# switch_vn9e30f.net
KiCad netlist of a schematic drawn in Altium Designer
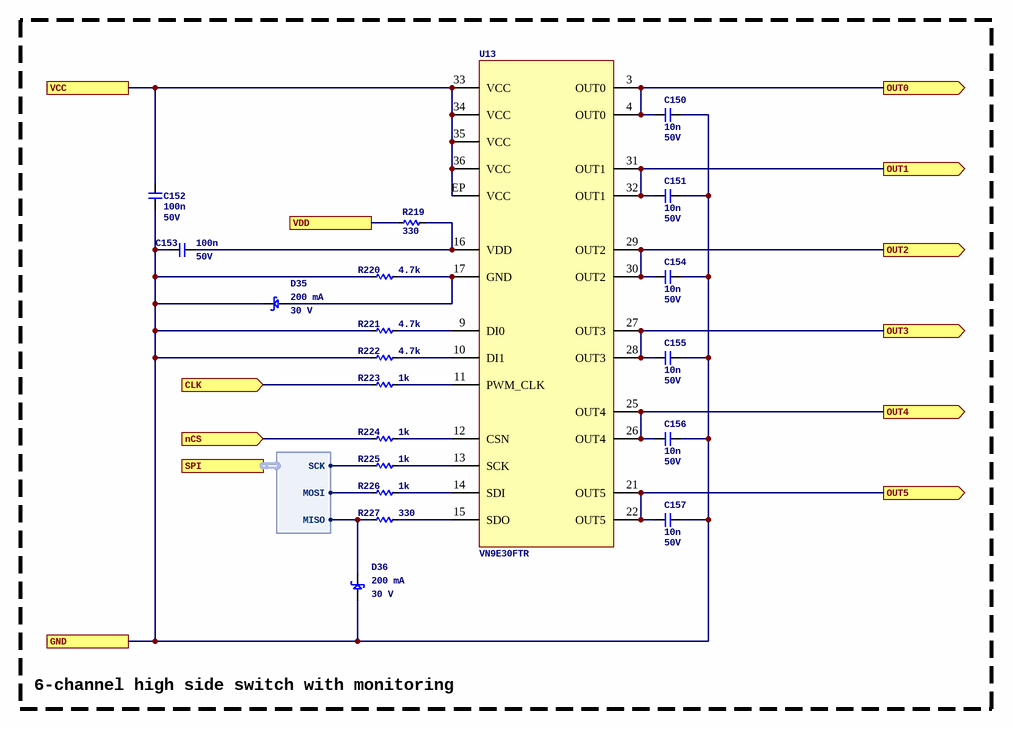
[diagram p0: switch_vn9e30f.SchDoc]

(export (version "E")
  (design (tool "Eeschema 10.0.6"))
  (components
    (comp (ref "C150")
      (value "CL05B103KB5NNNC")
      (footprint "C0402")
      (fields
        (field (name "CAPACITANCE") "10n")
        (field (name "MANUFACTURER") "Samsung Electro-Mechanics")
        (field (name "VOLTAGE RATING") "50V")
      )
      (libsource (lib "database") (part "__template_cap"))
    )
    (comp (ref "C151")
      (value "CL05B103KB5NNNC")
      (footprint "C0402")
      (fields
        (field (name "CAPACITANCE") "10n")
        (field (name "MANUFACTURER") "Samsung Electro-Mechanics")
        (field (name "VOLTAGE RATING") "50V")
      )
      (libsource (lib "database") (part "__template_cap"))
    )
    (comp (ref "C152")
      (value "CL05B104KB54PNC")
      (footprint "C0402")
      (fields
        (field (name "CAPACITANCE") "100n")
        (field (name "MANUFACTURER") "Samsung Electro-Mechanics")
        (field (name "VOLTAGE RATING") "50V")
      )
      (libsource (lib "database") (part "__template_cap"))
    )
    (comp (ref "C153")
      (value "CL05B104KB54PNC")
      (footprint "C0402")
      (fields
        (field (name "CAPACITANCE") "100n")
        (field (name "MANUFACTURER") "Samsung Electro-Mechanics")
        (field (name "VOLTAGE RATING") "50V")
      )
      (libsource (lib "database") (part "__template_cap"))
    )
    (comp (ref "C154")
      (value "CL05B103KB5NNNC")
      (footprint "C0402")
      (fields
        (field (name "CAPACITANCE") "10n")
        (field (name "MANUFACTURER") "Samsung Electro-Mechanics")
        (field (name "VOLTAGE RATING") "50V")
      )
      (libsource (lib "database") (part "__template_cap"))
    )
    (comp (ref "C155")
      (value "CL05B103KB5NNNC")
      (footprint "C0402")
      (fields
        (field (name "CAPACITANCE") "10n")
        (field (name "MANUFACTURER") "Samsung Electro-Mechanics")
        (field (name "VOLTAGE RATING") "50V")
      )
      (libsource (lib "database") (part "__template_cap"))
    )
    (comp (ref "C156")
      (value "CL05B103KB5NNNC")
      (footprint "C0402")
      (fields
        (field (name "CAPACITANCE") "10n")
        (field (name "MANUFACTURER") "Samsung Electro-Mechanics")
        (field (name "VOLTAGE RATING") "50V")
      )
      (libsource (lib "database") (part "__template_cap"))
    )
    (comp (ref "C157")
      (value "CL05B103KB5NNNC")
      (footprint "C0402")
      (fields
        (field (name "CAPACITANCE") "10n")
        (field (name "MANUFACTURER") "Samsung Electro-Mechanics")
        (field (name "VOLTAGE RATING") "50V")
      )
      (libsource (lib "database") (part "__template_cap"))
    )
    (comp (ref "D35")
      (value "BAT54XV2T1G")
      (footprint "SOD523")
      (description "ON Semi BAT54XV2T1G; SMT Schottky Diode; 30V 200mA; 5ns; 2-Pin SOD-523")
      (fields
        (field (name "MANUFACTURER") "onsemi")
        (field (name "CURRENT") "200 mA")
        (field (name "VOLTAGE") "30 V")
      )
      (libsource (lib "SSCP") (part "SCHOTTKY_30V_BAT54XV2T1G"))
    )
    (comp (ref "D36")
      (value "BAT54XV2T1G")
      (footprint "SOD523")
      (description "ON Semi BAT54XV2T1G; SMT Schottky Diode; 30V 200mA; 5ns; 2-Pin SOD-523")
      (fields
        (field (name "MANUFACTURER") "onsemi")
        (field (name "CURRENT") "200 mA")
        (field (name "VOLTAGE") "30 V")
      )
      (libsource (lib "SSCP") (part "SCHOTTKY_30V_BAT54XV2T1G"))
    )
    (comp (ref "R219")
      (value "330")
      (footprint "R0402")
      (fields
        (field (name "TOLERANCE") "1%")
        (field (name "MANUFACTURER PART NUMBER") "0402WGF3300TCE")
        (field (name "MANUFACTURER") "UNI-ROYAL(Uniroyal Elec)")
      )
      (libsource (lib "database") (part "__template_resistor"))
    )
    (comp (ref "R220")
      (value "4.7k")
      (footprint "R0402")
      (fields
        (field (name "TOLERANCE") "1%")
        (field (name "MANUFACTURER PART NUMBER") "0402WGF4701TCE")
        (field (name "MANUFACTURER") "UNI-ROYAL(Uniroyal Elec)")
      )
      (libsource (lib "database") (part "__template_resistor"))
    )
    (comp (ref "R221")
      (value "4.7k")
      (footprint "R0402")
      (fields
        (field (name "TOLERANCE") "1%")
        (field (name "MANUFACTURER PART NUMBER") "0402WGF4701TCE")
        (field (name "MANUFACTURER") "UNI-ROYAL(Uniroyal Elec)")
      )
      (libsource (lib "database") (part "__template_resistor"))
    )
    (comp (ref "R222")
      (value "4.7k")
      (footprint "R0402")
      (fields
        (field (name "TOLERANCE") "1%")
        (field (name "MANUFACTURER PART NUMBER") "0402WGF4701TCE")
        (field (name "MANUFACTURER") "UNI-ROYAL(Uniroyal Elec)")
      )
      (libsource (lib "database") (part "__template_resistor"))
    )
    (comp (ref "R223")
      (value "1k")
      (footprint "R0402")
      (fields
        (field (name "TOLERANCE") "1%")
        (field (name "MANUFACTURER PART NUMBER") "0402WGF1001TCE")
        (field (name "MANUFACTURER") "UNI-ROYAL(Uniroyal Elec)")
      )
      (libsource (lib "database") (part "__template_resistor"))
    )
    (comp (ref "R224")
      (value "1k")
      (footprint "R0402")
      (fields
        (field (name "TOLERANCE") "1%")
        (field (name "MANUFACTURER PART NUMBER") "0402WGF1001TCE")
        (field (name "MANUFACTURER") "UNI-ROYAL(Uniroyal Elec)")
      )
      (libsource (lib "database") (part "__template_resistor"))
    )
    (comp (ref "R225")
      (value "1k")
      (footprint "R0402")
      (fields
        (field (name "TOLERANCE") "1%")
        (field (name "MANUFACTURER PART NUMBER") "0402WGF1001TCE")
        (field (name "MANUFACTURER") "UNI-ROYAL(Uniroyal Elec)")
      )
      (libsource (lib "database") (part "__template_resistor"))
    )
    (comp (ref "R226")
      (value "1k")
      (footprint "R0402")
      (fields
        (field (name "TOLERANCE") "1%")
        (field (name "MANUFACTURER PART NUMBER") "0402WGF1001TCE")
        (field (name "MANUFACTURER") "UNI-ROYAL(Uniroyal Elec)")
      )
      (libsource (lib "database") (part "__template_resistor"))
    )
    (comp (ref "R227")
      (value "330")
      (footprint "R0402")
      (fields
        (field (name "TOLERANCE") "1%")
        (field (name "MANUFACTURER PART NUMBER") "0402WGF3300TCE")
        (field (name "MANUFACTURER") "UNI-ROYAL(Uniroyal Elec)")
      )
      (libsource (lib "database") (part "__template_resistor"))
    )
    (comp (ref "U13")
      (value "VN9E30FTR")
      (footprint "ST_ECOPACK_QFN50P600X600X90-32N")
      (description "Power Switch/Driver 1:6 N-Channel 35A 32-QFN (6x6)")
      (fields (field (name "MANUFACTURER") "STMicroelectronics"))
      (libsource (lib "SSCP") (part "LOADSWITCH_VN9E30FTR"))
    )
  )
  (nets
    (net (code "2") (name "/CLK") (class "Default") (node (ref "R223") (pin "2") (pintype "passive")))
    (net (code "3") (name "/GND") (class "Default")
      (node (ref "C150") (pin "2") (pintype "passive"))
      (node (ref "C151") (pin "2") (pintype "passive"))
      (node (ref "C152") (pin "2") (pintype "passive"))
      (node (ref "C153") (pin "2") (pintype "passive"))
      (node (ref "C154") (pin "2") (pintype "passive"))
      (node (ref "C155") (pin "2") (pintype "passive"))
      (node (ref "C156") (pin "2") (pintype "passive"))
      (node (ref "C157") (pin "2") (pintype "passive"))
      (node (ref "D35") (pin "2") (pintype "passive"))
      (node (ref "D36") (pin "1") (pintype "passive"))
      (node (ref "R220") (pin "2") (pintype "passive"))
      (node (ref "R221") (pin "2") (pintype "passive"))
      (node (ref "R222") (pin "2") (pintype "passive"))
    )
    (net (code "4") (name "/MISO") (class "Default")
      (node (ref "D36") (pin "2") (pintype "passive"))
      (node (ref "R227") (pin "1") (pintype "passive"))
    )
    (net (code "5") (name "/MOSI") (class "Default") (node (ref "R226") (pin "2") (pintype "passive")))
    (net (code "6") (name "/OUT0") (class "Default")
      (node (ref "C150") (pin "1") (pintype "passive"))
      (node (ref "U13") (pin "3") (pinfunction "OUT0_3") (pintype "passive"))
      (node (ref "U13") (pin "4") (pinfunction "OUT0_4") (pintype "passive"))
    )
    (net (code "7") (name "/OUT1") (class "Default")
      (node (ref "C151") (pin "1") (pintype "passive"))
      (node (ref "U13") (pin "31") (pinfunction "OUT1_31") (pintype "passive"))
      (node (ref "U13") (pin "32") (pinfunction "OUT1_32") (pintype "passive"))
    )
    (net (code "8") (name "/OUT2") (class "Default")
      (node (ref "C154") (pin "1") (pintype "passive"))
      (node (ref "U13") (pin "29") (pinfunction "OUT2_29") (pintype "passive"))
      (node (ref "U13") (pin "30") (pinfunction "OUT2_30") (pintype "passive"))
    )
    (net (code "9") (name "/OUT3") (class "Default")
      (node (ref "C155") (pin "1") (pintype "passive"))
      (node (ref "U13") (pin "27") (pinfunction "OUT3_27") (pintype "passive"))
      (node (ref "U13") (pin "28") (pinfunction "OUT3_28") (pintype "passive"))
    )
    (net (code "10") (name "/OUT4") (class "Default")
      (node (ref "C156") (pin "1") (pintype "passive"))
      (node (ref "U13") (pin "25") (pinfunction "OUT4_25") (pintype "passive"))
      (node (ref "U13") (pin "26") (pinfunction "OUT4_26") (pintype "passive"))
    )
    (net (code "11") (name "/OUT5") (class "Default")
      (node (ref "C157") (pin "1") (pintype "passive"))
      (node (ref "U13") (pin "21") (pinfunction "OUT5_21") (pintype "passive"))
      (node (ref "U13") (pin "22") (pinfunction "OUT5_22") (pintype "passive"))
    )
    (net (code "12") (name "/SCK") (class "Default") (node (ref "R225") (pin "2") (pintype "passive")))
    (net (code "13") (name "/VCC") (class "Default")
      (node (ref "C152") (pin "1") (pintype "passive"))
      (node (ref "U13") (pin "33") (pinfunction "VCC_33") (pintype "passive"))
      (node (ref "U13") (pin "34") (pinfunction "VCC_34") (pintype "passive"))
      (node (ref "U13") (pin "35") (pinfunction "VCC_35") (pintype "passive"))
      (node (ref "U13") (pin "36") (pinfunction "VCC_36") (pintype "passive"))
      (node (ref "U13") (pin "EP") (pinfunction "VCC_EP") (pintype "passive"))
    )
    (net (code "14") (name "/VDD") (class "Default") (node (ref "R219") (pin "1") (pintype "passive")))
    (net (code "15") (name "/nCS") (class "Default") (node (ref "R224") (pin "2") (pintype "passive")))
    (net (code "17") (name "Net-(U13-CSN)") (class "Default")
      (node (ref "R224") (pin "1") (pintype "passive"))
      (node (ref "U13") (pin "12") (pinfunction "CSN_12") (pintype "passive"))
    )
    (net (code "18") (name "Net-(U13-DI0)") (class "Default")
      (node (ref "R221") (pin "1") (pintype "passive"))
      (node (ref "U13") (pin "9") (pinfunction "DI0_9") (pintype "passive"))
    )
    (net (code "19") (name "Net-(U13-DI1)") (class "Default")
      (node (ref "R222") (pin "1") (pintype "passive"))
      (node (ref "U13") (pin "10") (pinfunction "DI1_10") (pintype "passive"))
    )
    (net (code "20") (name "Net-(U13-GND)") (class "Default")
      (node (ref "D35") (pin "1") (pintype "passive"))
      (node (ref "R220") (pin "1") (pintype "passive"))
      (node (ref "U13") (pin "17") (pinfunction "GND_17") (pintype "passive"))
    )
    (net (code "21") (name "Net-(U13-PWM_CLK)") (class "Default")
      (node (ref "R223") (pin "1") (pintype "passive"))
      (node (ref "U13") (pin "11") (pinfunction "PWM_CLK_11") (pintype "passive"))
    )
    (net (code "22") (name "Net-(U13-SCK)") (class "Default")
      (node (ref "R225") (pin "1") (pintype "passive"))
      (node (ref "U13") (pin "13") (pinfunction "SCK_13") (pintype "passive"))
    )
    (net (code "23") (name "Net-(U13-SDI)") (class "Default")
      (node (ref "R226") (pin "1") (pintype "passive"))
      (node (ref "U13") (pin "14") (pinfunction "SDI_14") (pintype "passive"))
    )
    (net (code "24") (name "Net-(U13-SDO)") (class "Default")
      (node (ref "R227") (pin "2") (pintype "passive"))
      (node (ref "U13") (pin "15") (pinfunction "SDO_15") (pintype "passive"))
    )
    (net (code "25") (name "Net-(U13-VDD)") (class "Default")
      (node (ref "C153") (pin "1") (pintype "passive"))
      (node (ref "R219") (pin "2") (pintype "passive"))
      (node (ref "U13") (pin "16") (pinfunction "VDD_16") (pintype "passive"))
    )
  )
)
